# trb-1_v1_1.net
KiCad netlist of a schematic drawn in EAGLE
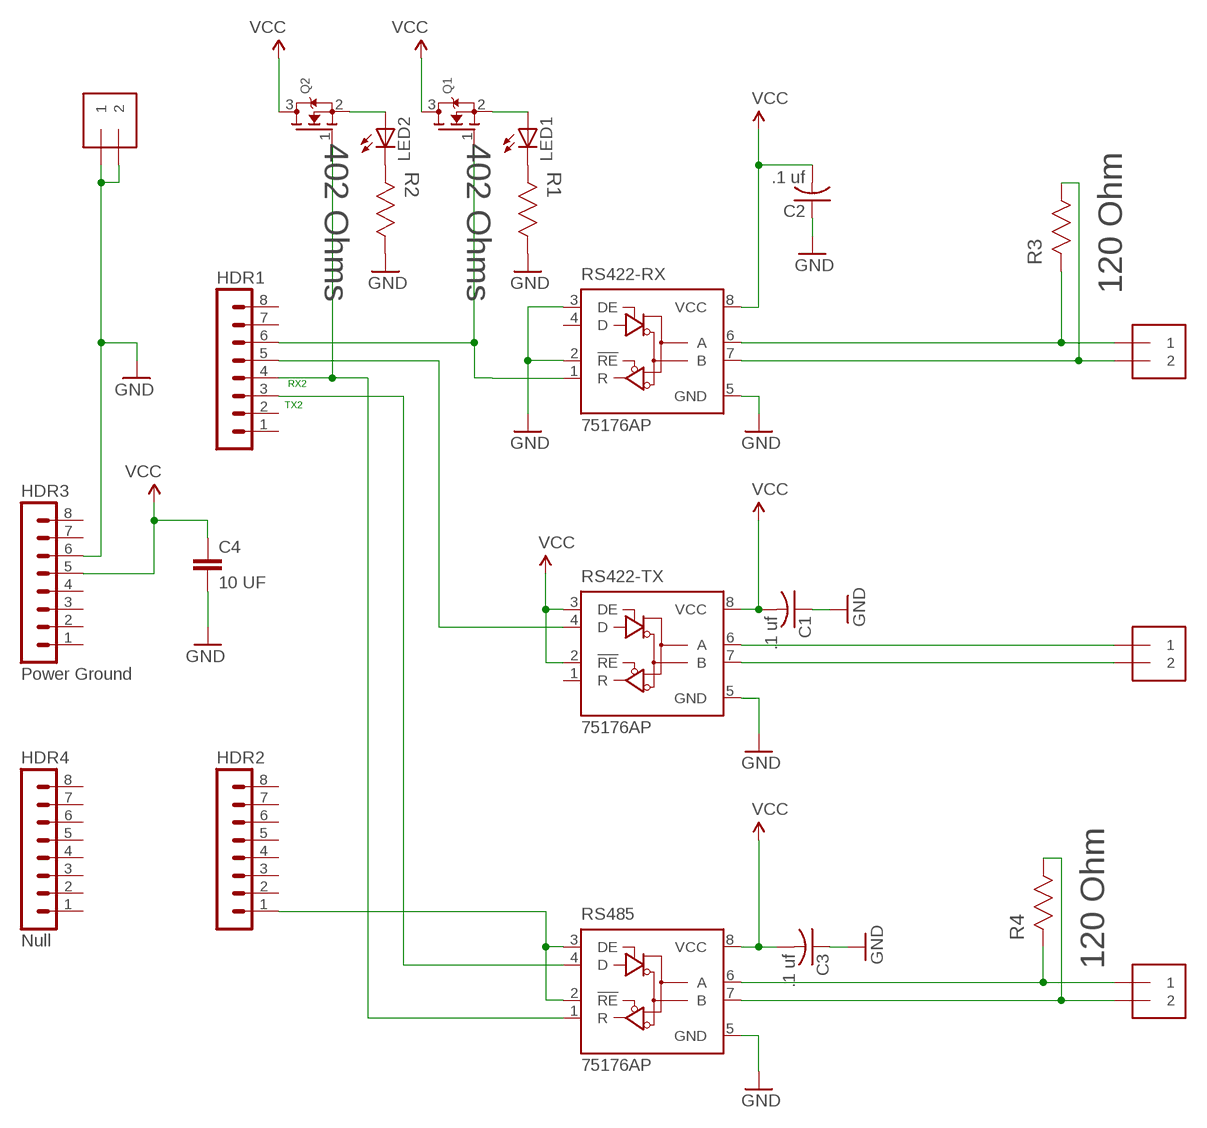
[diagram p0: schematic, sheet 1]

(export (version "E")
  (design (tool "Eeschema 10.0.6"))
  (components
    (comp (ref "C1")
      (value ".1 uf")
      (footprint "eagle-import:C0805")
      (libsource (lib "eagle-import") (part "C-USC0805"))
    )
    (comp (ref "C2")
      (value ".1 uf")
      (footprint "eagle-import:C0805")
      (libsource (lib "eagle-import") (part "C-USC0805"))
    )
    (comp (ref "C3")
      (value ".1 uf")
      (footprint "eagle-import:C0805")
      (libsource (lib "eagle-import") (part "C-USC0805"))
    )
    (comp (ref "C4")
      (value "10 UF")
      (footprint "eagle-import:0805-CAP")
      (libsource (lib "eagle-import") (part "10UF10V10%(0805)"))
    )
    (comp (ref "HDR1")
      (value "MA08-1")
      (footprint "eagle-import:MA08-1")
      (libsource (lib "eagle-import") (part "MA08-1"))
    )
    (comp (ref "HDR2")
      (value "MA08-1")
      (footprint "eagle-import:MA08-1")
      (libsource (lib "eagle-import") (part "MA08-1"))
    )
    (comp (ref "HDR3")
      (value "Power Ground")
      (footprint "eagle-import:MA08-1")
      (libsource (lib "eagle-import") (part "MA08-1"))
    )
    (comp (ref "HDR4")
      (value "Null")
      (footprint "eagle-import:MA08-1")
      (libsource (lib "eagle-import") (part "MA08-1"))
    )
    (comp (ref "J1")
      (value "1X2-3.5MM")
      (footprint "eagle-import:1X2-3.5MM")
      (libsource (lib "eagle-import") (part "1X2-3.5MM"))
    )
    (comp (ref "LED1")
      (value "LEDCHIP-LED0805")
      (footprint "eagle-import:CHIP-LED0805")
      (libsource (lib "eagle-import") (part "LEDCHIP-LED0805"))
    )
    (comp (ref "LED2")
      (value "LEDCHIP-LED0805")
      (footprint "eagle-import:CHIP-LED0805")
      (libsource (lib "eagle-import") (part "LEDCHIP-LED0805"))
    )
    (comp (ref "Q1")
      (value "MOSFET-NREFLOW")
      (footprint "eagle-import:SOT23")
      (libsource (lib "eagle-import") (part "MOSFET-NREFLOW"))
    )
    (comp (ref "Q2")
      (value "MOSFET-NREFLOW")
      (footprint "eagle-import:SOT23")
      (libsource (lib "eagle-import") (part "MOSFET-NREFLOW"))
    )
    (comp (ref "R1")
      (value "402 Ohms")
      (footprint "eagle-import:RESC2013X65N")
      (fields (field (name "MPN") "MCR10EZHF4020") (field (name "TOLERANCE") "±1%"))
      (libsource (lib "eagle-import") (part "MCR10EZHF4020"))
    )
    (comp (ref "R2")
      (value "402 Ohms")
      (footprint "eagle-import:RESC2013X65N")
      (fields (field (name "MPN") "MCR10EZHF4020") (field (name "TOLERANCE") "±1%"))
      (libsource (lib "eagle-import") (part "MCR10EZHF4020"))
    )
    (comp (ref "R3")
      (value "120 Ohm")
      (footprint "eagle-import:RESC2013X65N")
      (fields (field (name "MPN") "ERJ-6GEYJ121V") (field (name "TOLERANCE") "±5%"))
      (libsource (lib "eagle-import") (part "ERJ-6GEYJ121V"))
    )
    (comp (ref "R4")
      (value "120 Ohm")
      (footprint "eagle-import:RESC2013X65N")
      (fields (field (name "MPN") "ERJ-6GEYJ121V") (field (name "TOLERANCE") "±5%"))
      (libsource (lib "eagle-import") (part "ERJ-6GEYJ121V"))
    )
    (comp (ref "RS422-RX")
      (value "75176AP")
      (footprint "eagle-import:DIL08")
      (fields (field (name "MF") "TEXAS INSTRUMENTS") (field (name "MPN") "SN75176AP"))
      (libsource (lib "eagle-import") (part "75176AP"))
    )
    (comp (ref "RS422-RX1")
      (value "1X2-3.5MM")
      (footprint "eagle-import:1X2-3.5MM")
      (libsource (lib "eagle-import") (part "1X2-3.5MM"))
    )
    (comp (ref "RS422-TX")
      (value "75176AP")
      (footprint "eagle-import:DIL08")
      (fields (field (name "MF") "TEXAS INSTRUMENTS") (field (name "MPN") "SN75176AP"))
      (libsource (lib "eagle-import") (part "75176AP"))
    )
    (comp (ref "RS422-TX1")
      (value "1X2-3.5MM")
      (footprint "eagle-import:1X2-3.5MM")
      (libsource (lib "eagle-import") (part "1X2-3.5MM"))
    )
    (comp (ref "RS485")
      (value "75176AP")
      (footprint "eagle-import:DIL08")
      (fields (field (name "MF") "TEXAS INSTRUMENTS") (field (name "MPN") "SN75176AP"))
      (libsource (lib "eagle-import") (part "75176AP"))
    )
    (comp (ref "RS485-TXRX")
      (value "1X2-3.5MM")
      (footprint "eagle-import:1X2-3.5MM")
      (libsource (lib "eagle-import") (part "1X2-3.5MM"))
    )
  )
  (nets
    (net (code "1") (name "GND") (class "Default")
      (node (ref "C1") (pin "1") (pinfunction "1_1") (pintype "passive"))
      (node (ref "C2") (pin "1") (pinfunction "1_1") (pintype "passive"))
      (node (ref "C3") (pin "1") (pinfunction "1_1") (pintype "passive"))
      (node (ref "C4") (pin "2") (pinfunction "2_2") (pintype "passive"))
      (node (ref "HDR3") (pin "6") (pinfunction "6_6") (pintype "passive"))
      (node (ref "J1") (pin "1") (pinfunction "1_1") (pintype "passive"))
      (node (ref "J1") (pin "2") (pinfunction "2_2") (pintype "passive"))
      (node (ref "R1") (pin "1") (pinfunction "R1_1") (pintype "passive"))
      (node (ref "R2") (pin "1") (pinfunction "R1_1") (pintype "passive"))
      (node (ref "RS422-RX") (pin "2") (pinfunction "~{RE}_2") (pintype "input"))
      (node (ref "RS422-RX") (pin "3") (pinfunction "DE_3") (pintype "input"))
      (node (ref "RS422-RX") (pin "5") (pinfunction "GND_5") (pintype "power_in"))
      (node (ref "RS422-TX") (pin "5") (pinfunction "GND_5") (pintype "power_in"))
      (node (ref "RS485") (pin "5") (pinfunction "GND_5") (pintype "power_in"))
    )
    (net (code "2") (name "Net-(Q1-G)") (class "Default")
      (node (ref "HDR1") (pin "6") (pinfunction "6_6") (pintype "passive"))
      (node (ref "Q1") (pin "1") (pinfunction "G_1") (pintype "bidirectional"))
      (node (ref "RS422-RX") (pin "1") (pinfunction "R_1") (pintype "input"))
    )
    (net (code "3") (name "Net-(Q1-S)") (class "Default")
      (node (ref "LED1") (pin "A") (pinfunction "A_A") (pintype "passive"))
      (node (ref "Q1") (pin "2") (pinfunction "S_2") (pintype "bidirectional"))
    )
    (net (code "4") (name "Net-(Q2-G)") (class "Default")
      (node (ref "HDR1") (pin "4") (pinfunction "4_4") (pintype "passive"))
      (node (ref "Q2") (pin "1") (pinfunction "G_1") (pintype "bidirectional"))
      (node (ref "RS485") (pin "1") (pinfunction "R_1") (pintype "input"))
    )
    (net (code "5") (name "Net-(Q2-S)") (class "Default")
      (node (ref "LED2") (pin "A") (pinfunction "A_A") (pintype "passive"))
      (node (ref "Q2") (pin "2") (pinfunction "S_2") (pintype "bidirectional"))
    )
    (net (code "6") (name "Net-(R1-R2)") (class "Default")
      (node (ref "LED1") (pin "C") (pinfunction "C_C") (pintype "passive"))
      (node (ref "R1") (pin "2") (pinfunction "R2_2") (pintype "passive"))
    )
    (net (code "7") (name "Net-(R2-R2)") (class "Default")
      (node (ref "LED2") (pin "C") (pinfunction "C_C") (pintype "passive"))
      (node (ref "R2") (pin "2") (pinfunction "R2_2") (pintype "passive"))
    )
    (net (code "8") (name "Net-(R3-R1)") (class "Default")
      (node (ref "R3") (pin "1") (pinfunction "R1_1") (pintype "passive"))
      (node (ref "RS422-RX") (pin "7") (pinfunction "B_7") (pintype "output"))
      (node (ref "RS422-RX1") (pin "2") (pinfunction "2_2") (pintype "passive"))
    )
    (net (code "9") (name "Net-(R3-R2)") (class "Default")
      (node (ref "R3") (pin "2") (pinfunction "R2_2") (pintype "passive"))
      (node (ref "RS422-RX") (pin "6") (pinfunction "A_6") (pintype "output"))
      (node (ref "RS422-RX1") (pin "1") (pinfunction "1_1") (pintype "passive"))
    )
    (net (code "10") (name "Net-(R4-R1)") (class "Default")
      (node (ref "R4") (pin "1") (pinfunction "R1_1") (pintype "passive"))
      (node (ref "RS485") (pin "7") (pinfunction "B_7") (pintype "output"))
      (node (ref "RS485-TXRX") (pin "2") (pinfunction "2_2") (pintype "passive"))
    )
    (net (code "11") (name "Net-(R4-R2)") (class "Default")
      (node (ref "R4") (pin "2") (pinfunction "R2_2") (pintype "passive"))
      (node (ref "RS485") (pin "6") (pinfunction "A_6") (pintype "output"))
      (node (ref "RS485-TXRX") (pin "1") (pinfunction "1_1") (pintype "passive"))
    )
    (net (code "12") (name "Net-(RS422-TX-A)") (class "Default")
      (node (ref "RS422-TX") (pin "6") (pinfunction "A_6") (pintype "output"))
      (node (ref "RS422-TX1") (pin "1") (pinfunction "1_1") (pintype "passive"))
    )
    (net (code "13") (name "Net-(RS422-TX-B)") (class "Default")
      (node (ref "RS422-TX") (pin "7") (pinfunction "B_7") (pintype "output"))
      (node (ref "RS422-TX1") (pin "2") (pinfunction "2_2") (pintype "passive"))
    )
    (net (code "14") (name "Net-(RS422-TX-D)") (class "Default")
      (node (ref "HDR1") (pin "5") (pinfunction "5_5") (pintype "passive"))
      (node (ref "RS422-TX") (pin "4") (pinfunction "D_4") (pintype "input"))
    )
    (net (code "15") (name "Net-(RS485-D)") (class "Default")
      (node (ref "HDR1") (pin "3") (pinfunction "3_3") (pintype "passive"))
      (node (ref "RS485") (pin "4") (pinfunction "D_4") (pintype "input"))
    )
    (net (code "16") (name "Net-(RS485-DE)") (class "Default")
      (node (ref "HDR2") (pin "1") (pinfunction "1_1") (pintype "passive"))
      (node (ref "RS485") (pin "2") (pinfunction "~{RE}_2") (pintype "input"))
      (node (ref "RS485") (pin "3") (pinfunction "DE_3") (pintype "input"))
    )
    (net (code "17") (name "VCC") (class "Default")
      (node (ref "C1") (pin "2") (pinfunction "2_2") (pintype "passive"))
      (node (ref "C2") (pin "2") (pinfunction "2_2") (pintype "passive"))
      (node (ref "C3") (pin "2") (pinfunction "2_2") (pintype "passive"))
      (node (ref "C4") (pin "1") (pinfunction "1_1") (pintype "passive"))
      (node (ref "HDR3") (pin "5") (pinfunction "5_5") (pintype "passive"))
      (node (ref "Q1") (pin "3") (pinfunction "D_3") (pintype "bidirectional"))
      (node (ref "Q2") (pin "3") (pinfunction "D_3") (pintype "bidirectional"))
      (node (ref "RS422-RX") (pin "8") (pinfunction "VCC_8") (pintype "power_in"))
      (node (ref "RS422-TX") (pin "2") (pinfunction "~{RE}_2") (pintype "input"))
      (node (ref "RS422-TX") (pin "3") (pinfunction "DE_3") (pintype "input"))
      (node (ref "RS422-TX") (pin "8") (pinfunction "VCC_8") (pintype "power_in"))
      (node (ref "RS485") (pin "8") (pinfunction "VCC_8") (pintype "power_in"))
    )
    (net (code "18") (name "unconnected-(HDR1-Pad1)") (class "Default")
      (node (ref "HDR1") (pin "1") (pinfunction "1_1") (pintype "passive"))
    )
    (net (code "19") (name "unconnected-(HDR1-Pad2)") (class "Default")
      (node (ref "HDR1") (pin "2") (pinfunction "2_2") (pintype "passive"))
    )
    (net (code "20") (name "unconnected-(HDR1-Pad7)") (class "Default")
      (node (ref "HDR1") (pin "7") (pinfunction "7_7") (pintype "passive"))
    )
    (net (code "21") (name "unconnected-(HDR1-Pad8)") (class "Default")
      (node (ref "HDR1") (pin "8") (pinfunction "8_8") (pintype "passive"))
    )
    (net (code "22") (name "unconnected-(HDR2-Pad2)") (class "Default")
      (node (ref "HDR2") (pin "2") (pinfunction "2_2") (pintype "passive"))
    )
    (net (code "23") (name "unconnected-(HDR2-Pad3)") (class "Default")
      (node (ref "HDR2") (pin "3") (pinfunction "3_3") (pintype "passive"))
    )
    (net (code "24") (name "unconnected-(HDR2-Pad4)") (class "Default")
      (node (ref "HDR2") (pin "4") (pinfunction "4_4") (pintype "passive"))
    )
    (net (code "25") (name "unconnected-(HDR2-Pad5)") (class "Default")
      (node (ref "HDR2") (pin "5") (pinfunction "5_5") (pintype "passive"))
    )
    (net (code "26") (name "unconnected-(HDR2-Pad6)") (class "Default")
      (node (ref "HDR2") (pin "6") (pinfunction "6_6") (pintype "passive"))
    )
    (net (code "27") (name "unconnected-(HDR2-Pad7)") (class "Default")
      (node (ref "HDR2") (pin "7") (pinfunction "7_7") (pintype "passive"))
    )
    (net (code "28") (name "unconnected-(HDR2-Pad8)") (class "Default")
      (node (ref "HDR2") (pin "8") (pinfunction "8_8") (pintype "passive"))
    )
    (net (code "29") (name "unconnected-(HDR3-Pad1)") (class "Default")
      (node (ref "HDR3") (pin "1") (pinfunction "1_1") (pintype "passive"))
    )
    (net (code "30") (name "unconnected-(HDR3-Pad2)") (class "Default")
      (node (ref "HDR3") (pin "2") (pinfunction "2_2") (pintype "passive"))
    )
    (net (code "31") (name "unconnected-(HDR3-Pad3)") (class "Default")
      (node (ref "HDR3") (pin "3") (pinfunction "3_3") (pintype "passive"))
    )
    (net (code "32") (name "unconnected-(HDR3-Pad4)") (class "Default")
      (node (ref "HDR3") (pin "4") (pinfunction "4_4") (pintype "passive"))
    )
    (net (code "33") (name "unconnected-(HDR3-Pad7)") (class "Default")
      (node (ref "HDR3") (pin "7") (pinfunction "7_7") (pintype "passive"))
    )
    (net (code "34") (name "unconnected-(HDR3-Pad8)") (class "Default")
      (node (ref "HDR3") (pin "8") (pinfunction "8_8") (pintype "passive"))
    )
    (net (code "35") (name "unconnected-(HDR4-Pad1)") (class "Default")
      (node (ref "HDR4") (pin "1") (pinfunction "1_1") (pintype "passive"))
    )
    (net (code "36") (name "unconnected-(HDR4-Pad2)") (class "Default")
      (node (ref "HDR4") (pin "2") (pinfunction "2_2") (pintype "passive"))
    )
    (net (code "37") (name "unconnected-(HDR4-Pad3)") (class "Default")
      (node (ref "HDR4") (pin "3") (pinfunction "3_3") (pintype "passive"))
    )
    (net (code "38") (name "unconnected-(HDR4-Pad4)") (class "Default")
      (node (ref "HDR4") (pin "4") (pinfunction "4_4") (pintype "passive"))
    )
    (net (code "39") (name "unconnected-(HDR4-Pad5)") (class "Default")
      (node (ref "HDR4") (pin "5") (pinfunction "5_5") (pintype "passive"))
    )
    (net (code "40") (name "unconnected-(HDR4-Pad6)") (class "Default")
      (node (ref "HDR4") (pin "6") (pinfunction "6_6") (pintype "passive"))
    )
    (net (code "41") (name "unconnected-(HDR4-Pad7)") (class "Default")
      (node (ref "HDR4") (pin "7") (pinfunction "7_7") (pintype "passive"))
    )
    (net (code "42") (name "unconnected-(HDR4-Pad8)") (class "Default")
      (node (ref "HDR4") (pin "8") (pinfunction "8_8") (pintype "passive"))
    )
    (net (code "43") (name "unconnected-(RS422-RX-D-Pad4)") (class "Default")
      (node (ref "RS422-RX") (pin "4") (pinfunction "D_4") (pintype "input"))
    )
    (net (code "44") (name "unconnected-(RS422-TX-R-Pad1)") (class "Default")
      (node (ref "RS422-TX") (pin "1") (pinfunction "R_1") (pintype "input"))
    )
  )
)
